# Scheme.net
KiCad netlist of a schematic drawn in EAGLE
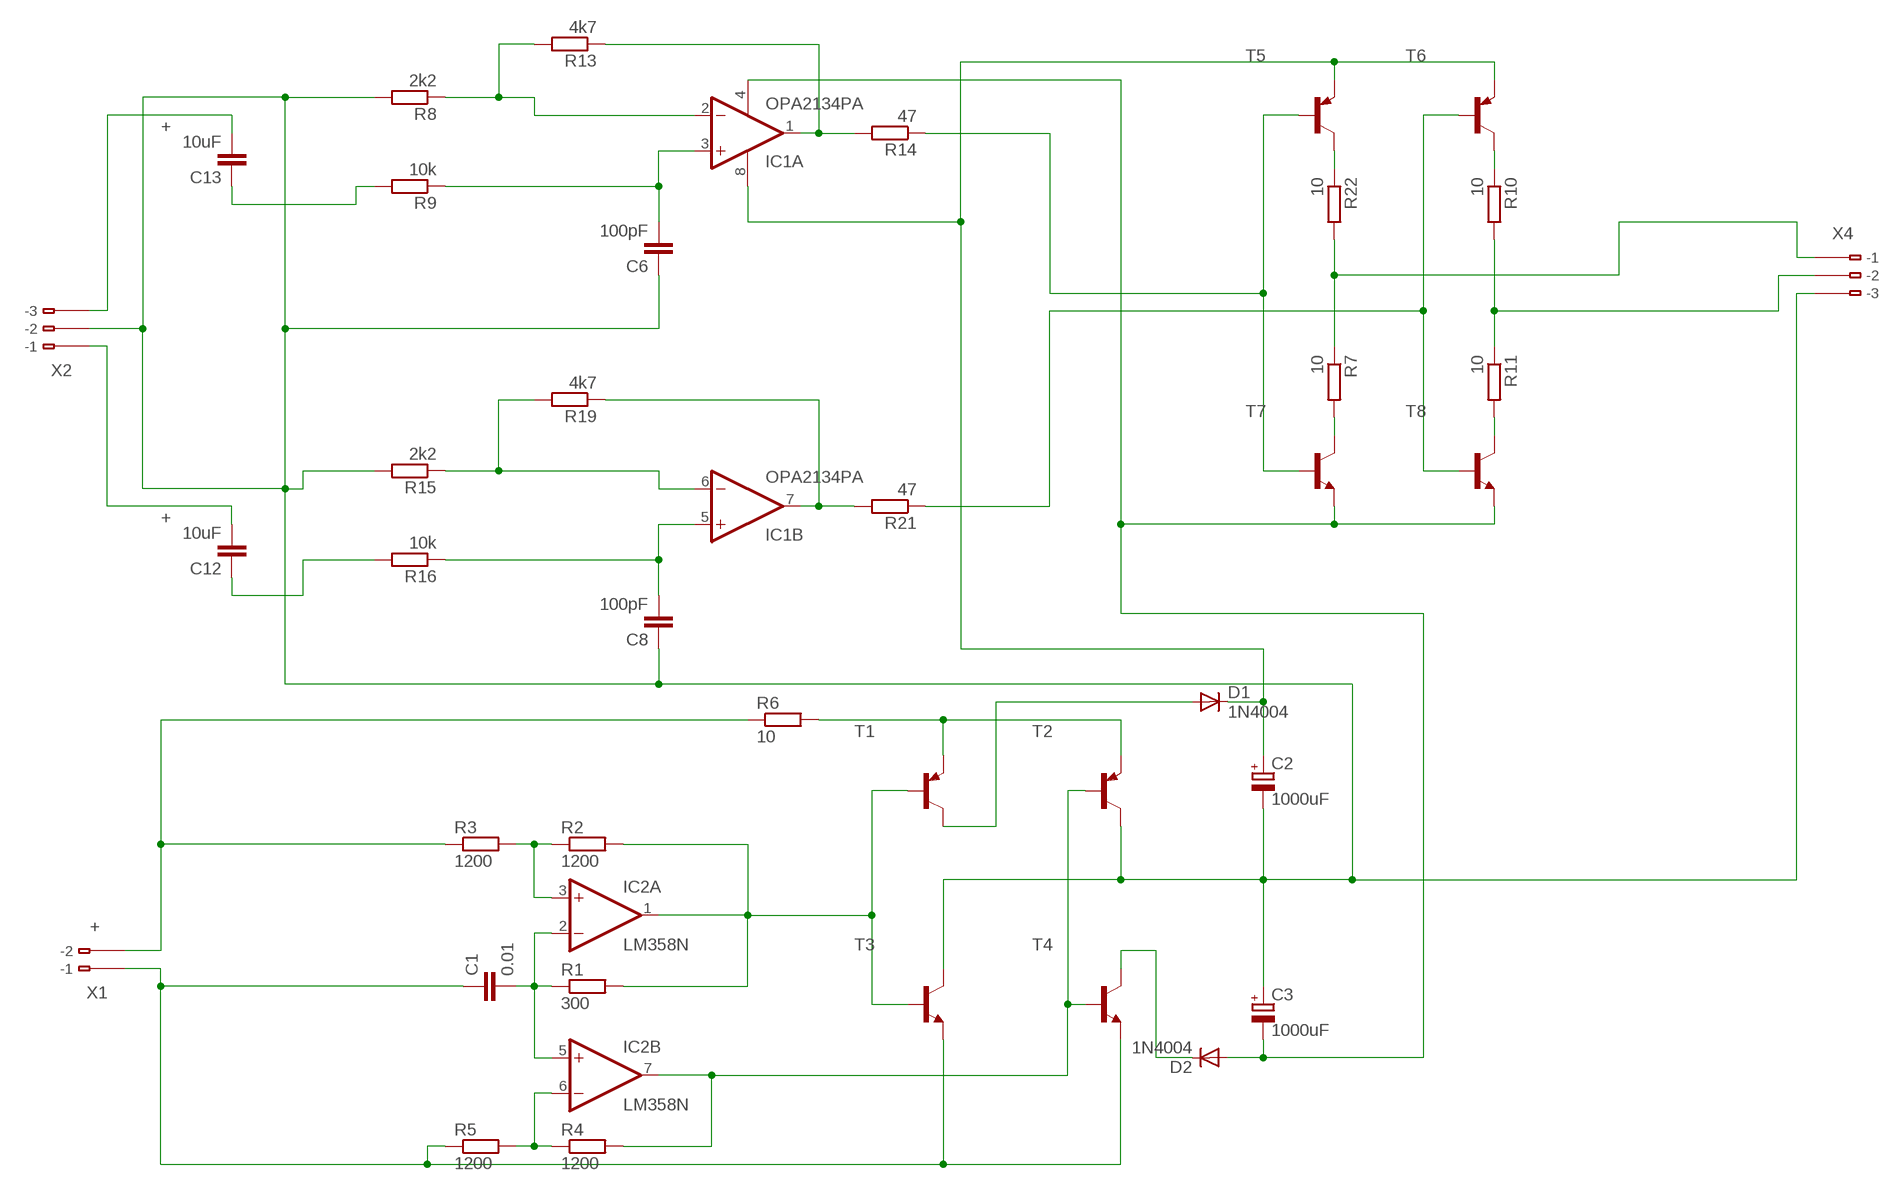
[diagram p0: schematic, sheet 1]

(export (version "E")
  (design (tool "Eeschema 10.0.6"))
  (components
    (comp (ref "C1")
      (value "0.01")
      (footprint "eagle-import:C025-060X050")
      (libsource (lib "eagle-import") (part "C-EU025-060X050"))
    )
    (comp (ref "C2")
      (value "1000uF")
      (footprint "eagle-import:085CS_1AR")
      (libsource (lib "eagle-import") (part "CPOL-EU085CS-1AR"))
    )
    (comp (ref "C3")
      (value "1000uF")
      (footprint "eagle-import:085CS_1AR")
      (libsource (lib "eagle-import") (part "CPOL-EU085CS-1AR"))
    )
    (comp (ref "C6")
      (value "100pF")
      (footprint "eagle-import:C025-060X050")
      (libsource (lib "eagle-import") (part "C-EU025-060X050"))
    )
    (comp (ref "C8")
      (value "100pF")
      (footprint "eagle-import:C025-060X050")
      (libsource (lib "eagle-import") (part "C-EU025-060X050"))
    )
    (comp (ref "C12")
      (value "10uF")
      (footprint "eagle-import:C025-060X050")
      (libsource (lib "eagle-import") (part "C-EU025-060X050"))
    )
    (comp (ref "C13")
      (value "10uF")
      (footprint "eagle-import:C025-060X050")
      (libsource (lib "eagle-import") (part "C-EU025-060X050"))
    )
    (comp (ref "D1")
      (value "1N4004")
      (footprint "eagle-import:DO41-10")
      (libsource (lib "eagle-import") (part "1N4004"))
    )
    (comp (ref "D2")
      (value "1N4004")
      (footprint "eagle-import:DO41-10")
      (libsource (lib "eagle-import") (part "1N4004"))
    )
    (comp (ref "IC1")
      (value "OPA2134PA")
      (footprint "eagle-import:DIL08")
      (libsource (lib "eagle-import") (part "OPA2PA134"))
    )
    (comp (ref "IC2")
      (value "LM358N")
      (footprint "eagle-import:DIL08")
      (libsource (lib "eagle-import") (part "LM358N"))
    )
    (comp (ref "R1")
      (value "300")
      (footprint "eagle-import:0204V")
      (libsource (lib "eagle-import") (part "R-EU_0204/2V"))
    )
    (comp (ref "R2")
      (value "1200")
      (footprint "eagle-import:0204V")
      (libsource (lib "eagle-import") (part "R-EU_0204/2V"))
    )
    (comp (ref "R3")
      (value "1200")
      (footprint "eagle-import:0204V")
      (libsource (lib "eagle-import") (part "R-EU_0204/2V"))
    )
    (comp (ref "R4")
      (value "1200")
      (footprint "eagle-import:0204V")
      (libsource (lib "eagle-import") (part "R-EU_0204/2V"))
    )
    (comp (ref "R5")
      (value "1200")
      (footprint "eagle-import:0204V")
      (libsource (lib "eagle-import") (part "R-EU_0204/2V"))
    )
    (comp (ref "R6")
      (value "10")
      (footprint "eagle-import:0204V")
      (libsource (lib "eagle-import") (part "R-EU_0204/2V"))
    )
    (comp (ref "R7")
      (value "10")
      (footprint "eagle-import:0204V")
      (libsource (lib "eagle-import") (part "R-EU_0204/2V"))
    )
    (comp (ref "R8")
      (value "2k2")
      (footprint "eagle-import:0204V")
      (libsource (lib "eagle-import") (part "R-EU_0204/2V"))
    )
    (comp (ref "R9")
      (value "10k")
      (footprint "eagle-import:0204V")
      (libsource (lib "eagle-import") (part "R-EU_0204/2V"))
    )
    (comp (ref "R10")
      (value "10")
      (footprint "eagle-import:0204V")
      (libsource (lib "eagle-import") (part "R-EU_0204/2V"))
    )
    (comp (ref "R11")
      (value "10")
      (footprint "eagle-import:0204V")
      (libsource (lib "eagle-import") (part "R-EU_0204/2V"))
    )
    (comp (ref "R13")
      (value "4k7")
      (footprint "eagle-import:0204V")
      (libsource (lib "eagle-import") (part "R-EU_0204/2V"))
    )
    (comp (ref "R14")
      (value "47")
      (footprint "eagle-import:0204V")
      (libsource (lib "eagle-import") (part "R-EU_0204/2V"))
    )
    (comp (ref "R15")
      (value "2k2")
      (footprint "eagle-import:0204V")
      (libsource (lib "eagle-import") (part "R-EU_0204/2V"))
    )
    (comp (ref "R16")
      (value "10k")
      (footprint "eagle-import:0204V")
      (libsource (lib "eagle-import") (part "R-EU_0204/2V"))
    )
    (comp (ref "R19")
      (value "4k7")
      (footprint "eagle-import:0204V")
      (libsource (lib "eagle-import") (part "R-EU_0204/2V"))
    )
    (comp (ref "R21")
      (value "47")
      (footprint "eagle-import:0204V")
      (libsource (lib "eagle-import") (part "R-EU_0204/2V"))
    )
    (comp (ref "R22")
      (value "10")
      (footprint "eagle-import:0204V")
      (libsource (lib "eagle-import") (part "R-EU_0204/2V"))
    )
    (comp (ref "T1")
      (value "2N4403-PNP-TO92-EBC")
      (footprint "eagle-import:TO92-EBC")
      (libsource (lib "eagle-import") (part "-PNP-TO92-EBC2N4403"))
    )
    (comp (ref "T2")
      (value "2N4403-PNP-TO92-EBC")
      (footprint "eagle-import:TO92-EBC")
      (libsource (lib "eagle-import") (part "-PNP-TO92-EBC2N4403"))
    )
    (comp (ref "T3")
      (value "2N4401-NPN-TO92-EBC")
      (footprint "eagle-import:TO92-EBC")
      (libsource (lib "eagle-import") (part "-NPN-TO92-EBC2N4401"))
    )
    (comp (ref "T4")
      (value "2N4401-NPN-TO92-EBC")
      (footprint "eagle-import:TO92-EBC")
      (libsource (lib "eagle-import") (part "-NPN-TO92-EBC2N4401"))
    )
    (comp (ref "T5")
      (value "2N4403-PNP-TO92-EBC")
      (footprint "eagle-import:TO92-EBC")
      (libsource (lib "eagle-import") (part "-PNP-TO92-EBC2N4403"))
    )
    (comp (ref "T6")
      (value "2N4403-PNP-TO92-EBC")
      (footprint "eagle-import:TO92-EBC")
      (libsource (lib "eagle-import") (part "-PNP-TO92-EBC2N4403"))
    )
    (comp (ref "T7")
      (value "2N4401-NPN-TO92-EBC")
      (footprint "eagle-import:TO92-EBC")
      (libsource (lib "eagle-import") (part "-NPN-TO92-EBC2N4401"))
    )
    (comp (ref "T8")
      (value "2N4401-NPN-TO92-EBC")
      (footprint "eagle-import:TO92-EBC")
      (libsource (lib "eagle-import") (part "-NPN-TO92-EBC2N4401"))
    )
    (comp (ref "X1")
      (value "233-102")
      (footprint "eagle-import:233-102")
      (libsource (lib "eagle-import") (part "233-102"))
    )
    (comp (ref "X2")
      (value "233-103")
      (footprint "eagle-import:233-103")
      (libsource (lib "eagle-import") (part "233-103"))
    )
    (comp (ref "X4")
      (value "233-103")
      (footprint "eagle-import:233-103")
      (libsource (lib "eagle-import") (part "233-103"))
    )
  )
  (nets
    (net (code "1") (name "Net-(C12-Pad1)") (class "Default")
      (node (ref "C12") (pin "1") (pinfunction "1_1") (pintype "passive"))
      (node (ref "R16") (pin "2") (pinfunction "2_2") (pintype "passive"))
    )
    (net (code "2") (name "Net-(C13-Pad1)") (class "Default")
      (node (ref "C13") (pin "1") (pinfunction "1_1") (pintype "passive"))
      (node (ref "R9") (pin "2") (pinfunction "2_2") (pintype "passive"))
    )
    (net (code "3") (name "Net-(D1-PadA)") (class "Default")
      (node (ref "D1") (pin "A") (pinfunction "A_A") (pintype "passive"))
      (node (ref "T1") (pin "C") (pinfunction "C_C") (pintype "passive"))
    )
    (net (code "4") (name "Net-(D2-PadC)") (class "Default")
      (node (ref "D2") (pin "C") (pinfunction "C_C") (pintype "passive"))
      (node (ref "T4") (pin "C") (pinfunction "C_C") (pintype "passive"))
    )
    (net (code "5") (name "Net-(IC1A-+IN)") (class "Default")
      (node (ref "C6") (pin "2") (pinfunction "2_2") (pintype "passive"))
      (node (ref "IC1") (pin "3") (pinfunction "+IN_3") (pintype "input"))
      (node (ref "R9") (pin "1") (pinfunction "1_1") (pintype "passive"))
    )
    (net (code "6") (name "Net-(IC1A--IN)") (class "Default")
      (node (ref "IC1") (pin "2") (pinfunction "-IN_2") (pintype "input"))
      (node (ref "R13") (pin "2") (pinfunction "2_2") (pintype "passive"))
      (node (ref "R8") (pin "1") (pinfunction "1_1") (pintype "passive"))
    )
    (net (code "7") (name "Net-(IC1A-OUT)") (class "Default")
      (node (ref "IC1") (pin "1") (pinfunction "OUT_1") (pintype "output"))
      (node (ref "R13") (pin "1") (pinfunction "1_1") (pintype "passive"))
      (node (ref "R14") (pin "2") (pinfunction "2_2") (pintype "passive"))
    )
    (net (code "8") (name "Net-(IC1A-V+)") (class "Default")
      (node (ref "C2") (pin "+") (pinfunction "+_+") (pintype "passive"))
      (node (ref "D1") (pin "C") (pinfunction "C_C") (pintype "passive"))
      (node (ref "IC1") (pin "8") (pinfunction "V+_8") (pintype "power_in"))
      (node (ref "T5") (pin "E") (pinfunction "E_E") (pintype "passive"))
      (node (ref "T6") (pin "E") (pinfunction "E_E") (pintype "passive"))
    )
    (net (code "9") (name "Net-(IC1A-V-)") (class "Default")
      (node (ref "C3") (pin "-") (pinfunction "-_-") (pintype "passive"))
      (node (ref "D2") (pin "A") (pinfunction "A_A") (pintype "passive"))
      (node (ref "IC1") (pin "4") (pinfunction "V-_4") (pintype "power_in"))
      (node (ref "T7") (pin "E") (pinfunction "E_E") (pintype "passive"))
      (node (ref "T8") (pin "E") (pinfunction "E_E") (pintype "passive"))
    )
    (net (code "10") (name "Net-(IC1B-+IN)") (class "Default")
      (node (ref "C8") (pin "2") (pinfunction "2_2") (pintype "passive"))
      (node (ref "IC1") (pin "5") (pinfunction "+IN_5") (pintype "input"))
      (node (ref "R16") (pin "1") (pinfunction "1_1") (pintype "passive"))
    )
    (net (code "11") (name "Net-(IC1B--IN)") (class "Default")
      (node (ref "IC1") (pin "6") (pinfunction "-IN_6") (pintype "input"))
      (node (ref "R15") (pin "1") (pinfunction "1_1") (pintype "passive"))
      (node (ref "R19") (pin "2") (pinfunction "2_2") (pintype "passive"))
    )
    (net (code "12") (name "Net-(IC1B-OUT)") (class "Default")
      (node (ref "IC1") (pin "7") (pinfunction "OUT_7") (pintype "output"))
      (node (ref "R19") (pin "1") (pinfunction "1_1") (pintype "passive"))
      (node (ref "R21") (pin "2") (pinfunction "2_2") (pintype "passive"))
    )
    (net (code "13") (name "Net-(IC2A-+IN)") (class "Default")
      (node (ref "IC2") (pin "3") (pinfunction "+IN_3") (pintype "input"))
      (node (ref "R2") (pin "1") (pinfunction "1_1") (pintype "passive"))
      (node (ref "R3") (pin "2") (pinfunction "2_2") (pintype "passive"))
    )
    (net (code "14") (name "Net-(IC2A--IN)") (class "Default")
      (node (ref "C1") (pin "2") (pinfunction "2_2") (pintype "passive"))
      (node (ref "IC2") (pin "2") (pinfunction "-IN_2") (pintype "input"))
      (node (ref "IC2") (pin "5") (pinfunction "+IN_5") (pintype "input"))
      (node (ref "R1") (pin "1") (pinfunction "1_1") (pintype "passive"))
    )
    (net (code "15") (name "Net-(IC2A-OUT)") (class "Default")
      (node (ref "IC2") (pin "1") (pinfunction "OUT_1") (pintype "output"))
      (node (ref "R1") (pin "2") (pinfunction "2_2") (pintype "passive"))
      (node (ref "R2") (pin "2") (pinfunction "2_2") (pintype "passive"))
      (node (ref "T1") (pin "B") (pinfunction "B_B") (pintype "passive"))
      (node (ref "T3") (pin "B") (pinfunction "B_B") (pintype "passive"))
    )
    (net (code "16") (name "Net-(IC2B--IN)") (class "Default")
      (node (ref "IC2") (pin "6") (pinfunction "-IN_6") (pintype "input"))
      (node (ref "R4") (pin "1") (pinfunction "1_1") (pintype "passive"))
      (node (ref "R5") (pin "2") (pinfunction "2_2") (pintype "passive"))
    )
    (net (code "17") (name "Net-(IC2B-OUT)") (class "Default")
      (node (ref "IC2") (pin "7") (pinfunction "OUT_7") (pintype "output"))
      (node (ref "R4") (pin "2") (pinfunction "2_2") (pintype "passive"))
      (node (ref "T2") (pin "B") (pinfunction "B_B") (pintype "passive"))
      (node (ref "T4") (pin "B") (pinfunction "B_B") (pintype "passive"))
    )
    (net (code "18") (name "Net-(R6-Pad2)") (class "Default")
      (node (ref "R6") (pin "2") (pinfunction "2_2") (pintype "passive"))
      (node (ref "T1") (pin "E") (pinfunction "E_E") (pintype "passive"))
      (node (ref "T2") (pin "E") (pinfunction "E_E") (pintype "passive"))
    )
    (net (code "19") (name "Net-(R7-Pad2)") (class "Default")
      (node (ref "R7") (pin "2") (pinfunction "2_2") (pintype "passive"))
      (node (ref "T7") (pin "C") (pinfunction "C_C") (pintype "passive"))
    )
    (net (code "20") (name "Net-(R10-Pad1)") (class "Default")
      (node (ref "R10") (pin "1") (pinfunction "1_1") (pintype "passive"))
      (node (ref "T6") (pin "C") (pinfunction "C_C") (pintype "passive"))
    )
    (net (code "21") (name "Net-(R11-Pad2)") (class "Default")
      (node (ref "R11") (pin "2") (pinfunction "2_2") (pintype "passive"))
      (node (ref "T8") (pin "C") (pinfunction "C_C") (pintype "passive"))
    )
    (net (code "22") (name "Net-(R14-Pad1)") (class "Default")
      (node (ref "R14") (pin "1") (pinfunction "1_1") (pintype "passive"))
      (node (ref "T5") (pin "B") (pinfunction "B_B") (pintype "passive"))
      (node (ref "T7") (pin "B") (pinfunction "B_B") (pintype "passive"))
    )
    (net (code "23") (name "Net-(R21-Pad1)") (class "Default")
      (node (ref "R21") (pin "1") (pinfunction "1_1") (pintype "passive"))
      (node (ref "T6") (pin "B") (pinfunction "B_B") (pintype "passive"))
      (node (ref "T8") (pin "B") (pinfunction "B_B") (pintype "passive"))
    )
    (net (code "24") (name "Net-(R22-Pad1)") (class "Default")
      (node (ref "R22") (pin "1") (pinfunction "1_1") (pintype "passive"))
      (node (ref "T5") (pin "C") (pinfunction "C_C") (pintype "passive"))
    )
    (net (code "25") (name "Net-(X1-B-1)") (class "Default")
      (node (ref "C1") (pin "1") (pinfunction "1_1") (pintype "passive"))
      (node (ref "R5") (pin "1") (pinfunction "1_1") (pintype "passive"))
      (node (ref "T3") (pin "E") (pinfunction "E_E") (pintype "passive"))
      (node (ref "T4") (pin "E") (pinfunction "E_E") (pintype "passive"))
      (node (ref "X1") (pin "B1") (pinfunction "B-1_B1") (pintype "passive"))
    )
    (net (code "26") (name "Net-(X1-B-2)") (class "Default")
      (node (ref "R3") (pin "1") (pinfunction "1_1") (pintype "passive"))
      (node (ref "R6") (pin "1") (pinfunction "1_1") (pintype "passive"))
      (node (ref "X1") (pin "B2") (pinfunction "B-2_B2") (pintype "passive"))
    )
    (net (code "27") (name "Net-(X2-B-1)") (class "Default")
      (node (ref "C12") (pin "2") (pinfunction "2_2") (pintype "passive"))
      (node (ref "X2") (pin "B1") (pinfunction "B-1_B1") (pintype "passive"))
    )
    (net (code "28") (name "Net-(X2-B-2)") (class "Default")
      (node (ref "C2") (pin "-") (pinfunction "-_-") (pintype "passive"))
      (node (ref "C3") (pin "+") (pinfunction "+_+") (pintype "passive"))
      (node (ref "C6") (pin "1") (pinfunction "1_1") (pintype "passive"))
      (node (ref "C8") (pin "1") (pinfunction "1_1") (pintype "passive"))
      (node (ref "R15") (pin "2") (pinfunction "2_2") (pintype "passive"))
      (node (ref "R8") (pin "2") (pinfunction "2_2") (pintype "passive"))
      (node (ref "T2") (pin "C") (pinfunction "C_C") (pintype "passive"))
      (node (ref "T3") (pin "C") (pinfunction "C_C") (pintype "passive"))
      (node (ref "X2") (pin "B2") (pinfunction "B-2_B2") (pintype "passive"))
      (node (ref "X4") (pin "B3") (pinfunction "B-3_B3") (pintype "passive"))
    )
    (net (code "29") (name "Net-(X2-B-3)") (class "Default")
      (node (ref "C13") (pin "2") (pinfunction "2_2") (pintype "passive"))
      (node (ref "X2") (pin "B3") (pinfunction "B-3_B3") (pintype "passive"))
    )
    (net (code "30") (name "Net-(X4-B-1)") (class "Default")
      (node (ref "R22") (pin "2") (pinfunction "2_2") (pintype "passive"))
      (node (ref "R7") (pin "1") (pinfunction "1_1") (pintype "passive"))
      (node (ref "X4") (pin "B1") (pinfunction "B-1_B1") (pintype "passive"))
    )
    (net (code "31") (name "Net-(X4-B-2)") (class "Default")
      (node (ref "R10") (pin "2") (pinfunction "2_2") (pintype "passive"))
      (node (ref "R11") (pin "1") (pinfunction "1_1") (pintype "passive"))
      (node (ref "X4") (pin "B2") (pinfunction "B-2_B2") (pintype "passive"))
    )
    (net (code "32") (name "unconnected-(X1--1-PadA1)") (class "Default")
      (node (ref "X1") (pin "A1") (pinfunction "-1_A1") (pintype "passive"))
    )
    (net (code "33") (name "unconnected-(X1--2-PadA2)") (class "Default")
      (node (ref "X1") (pin "A2") (pinfunction "-2_A2") (pintype "passive"))
    )
    (net (code "34") (name "unconnected-(X2--1-PadA1)") (class "Default")
      (node (ref "X2") (pin "A1") (pinfunction "-1_A1") (pintype "passive"))
    )
    (net (code "35") (name "unconnected-(X2--2-PadA2)") (class "Default")
      (node (ref "X2") (pin "A2") (pinfunction "-2_A2") (pintype "passive"))
    )
    (net (code "36") (name "unconnected-(X2--3-PadA3)") (class "Default")
      (node (ref "X2") (pin "A3") (pinfunction "-3_A3") (pintype "passive"))
    )
    (net (code "37") (name "unconnected-(X4--1-PadA1)") (class "Default")
      (node (ref "X4") (pin "A1") (pinfunction "-1_A1") (pintype "passive"))
    )
    (net (code "38") (name "unconnected-(X4--2-PadA2)") (class "Default")
      (node (ref "X4") (pin "A2") (pinfunction "-2_A2") (pintype "passive"))
    )
    (net (code "39") (name "unconnected-(X4--3-PadA3)") (class "Default")
      (node (ref "X4") (pin "A3") (pinfunction "-3_A3") (pintype "passive"))
    )
  )
)
